# Greippi_pos_boost.net
KiCad netlist of a schematic drawn in EAGLE
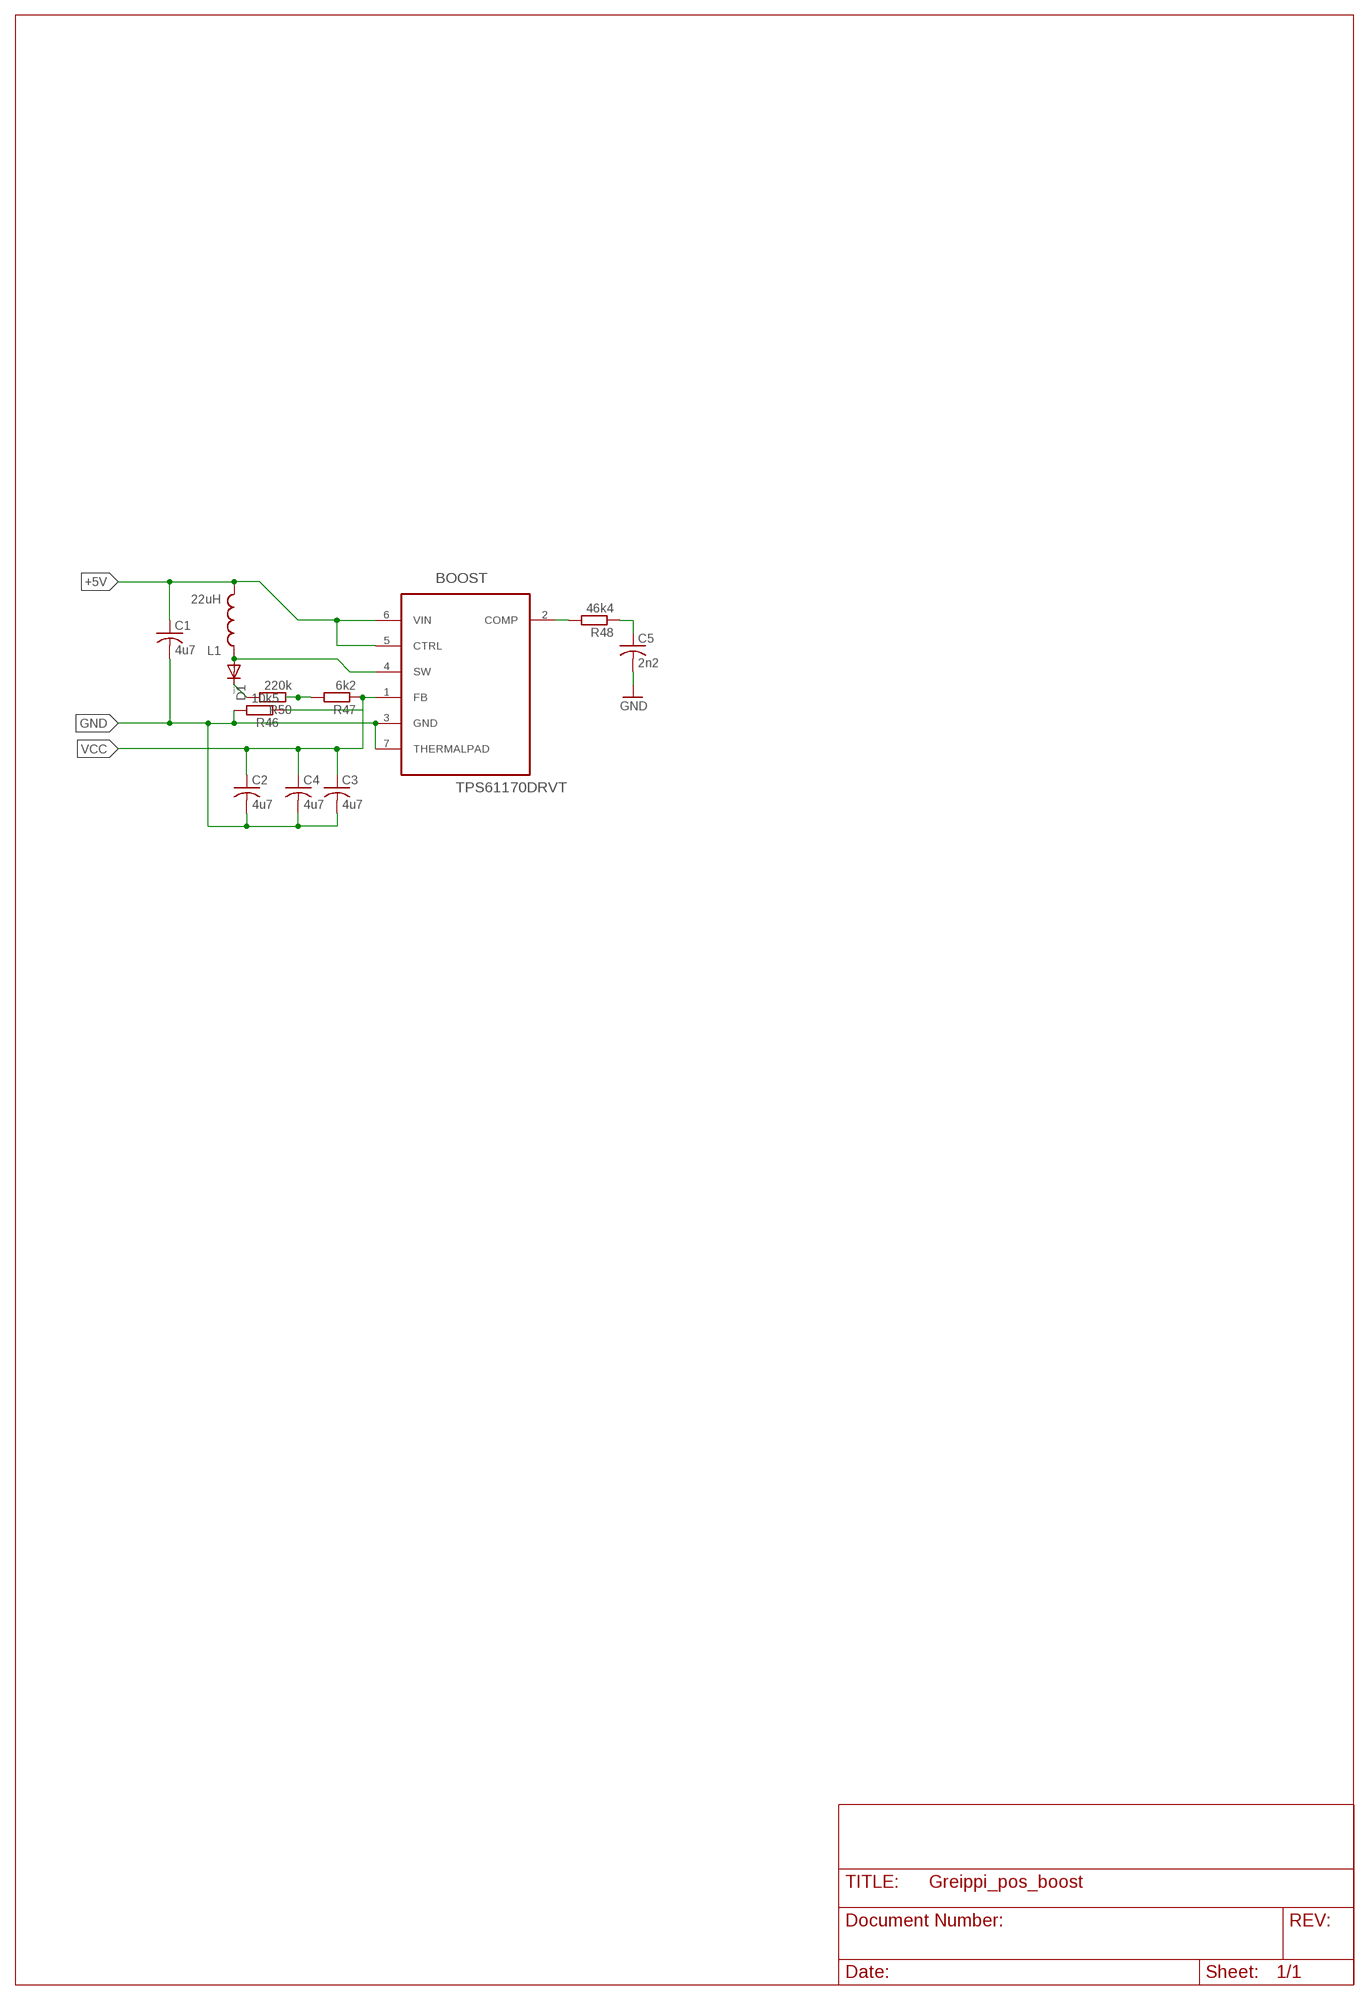
[diagram p0: schematic, sheet 1]

(export (version "E")
  (design (tool "Eeschema 10.0.6"))
  (components
    (comp (ref "BOOST")
      (value "TPS61170DRVT")
      (footprint "eagle-import:SON65P210X210X80-7N")
      (libsource (lib "eagle-import") (part "TPS61170DRVT"))
    )
    (comp (ref "C1")
      (value "4u7")
      (footprint "eagle-import:C1206")
      (libsource (lib "eagle-import") (part "C-USC1206"))
    )
    (comp (ref "C2")
      (value "4u7")
      (footprint "eagle-import:C0805")
      (libsource (lib "eagle-import") (part "C-USC0805"))
    )
    (comp (ref "C3")
      (value "4u7")
      (footprint "eagle-import:C1206")
      (libsource (lib "eagle-import") (part "C-USC1206"))
    )
    (comp (ref "C4")
      (value "4u7")
      (footprint "eagle-import:C1206")
      (libsource (lib "eagle-import") (part "C-USC1206"))
    )
    (comp (ref "C5")
      (value "2n2")
      (footprint "eagle-import:C1206")
      (libsource (lib "eagle-import") (part "C-USC1206"))
    )
    (comp (ref "D1")
      (value "DIODE-SOD123")
      (footprint "eagle-import:SOD123")
      (libsource (lib "eagle-import") (part "DIODE-SOD123"))
    )
    (comp (ref "L1")
      (value "22uH")
      (footprint "eagle-import:SRN6045")
      (libsource (lib "eagle-import") (part "INDUCTORBOURNS_SRN6045"))
    )
    (comp (ref "R46")
      (value "10k5")
      (footprint "eagle-import:R0805")
      (libsource (lib "eagle-import") (part "R-EU_R0805"))
    )
    (comp (ref "R47")
      (value "6k2")
      (footprint "eagle-import:R0805")
      (libsource (lib "eagle-import") (part "R-EU_R0805"))
    )
    (comp (ref "R48")
      (value "46k4")
      (footprint "eagle-import:R0805")
      (libsource (lib "eagle-import") (part "R-EU_R0805"))
    )
    (comp (ref "R50")
      (value "220k")
      (footprint "eagle-import:R0805")
      (libsource (lib "eagle-import") (part "R-EU_R0805"))
    )
  )
  (nets
    (net (code "1") (name "+5V") (class "Default")
      (node (ref "BOOST") (pin "5") (pinfunction "CTRL_5") (pintype "input"))
      (node (ref "BOOST") (pin "6") (pinfunction "VIN_6") (pintype "power_in"))
      (node (ref "C1") (pin "1") (pinfunction "1_1") (pintype "passive"))
      (node (ref "L1") (pin "2") (pinfunction "2_2") (pintype "passive"))
    )
    (net (code "2") (name "GND") (class "Default")
      (node (ref "BOOST") (pin "3") (pinfunction "GND_3") (pintype "passive"))
      (node (ref "BOOST") (pin "7") (pinfunction "THERMALPAD_7") (pintype "passive"))
      (node (ref "C1") (pin "2") (pinfunction "2_2") (pintype "passive"))
      (node (ref "C2") (pin "2") (pinfunction "2_2") (pintype "passive"))
      (node (ref "C3") (pin "2") (pinfunction "2_2") (pintype "passive"))
      (node (ref "C4") (pin "2") (pinfunction "2_2") (pintype "passive"))
      (node (ref "C5") (pin "2") (pinfunction "2_2") (pintype "passive"))
      (node (ref "R46") (pin "2") (pinfunction "2_2") (pintype "passive"))
    )
    (net (code "3") (name "Net-(BOOST-COMP)") (class "Default")
      (node (ref "BOOST") (pin "2") (pinfunction "COMP_2") (pintype "output"))
      (node (ref "R48") (pin "2") (pinfunction "2_2") (pintype "passive"))
    )
    (net (code "4") (name "Net-(BOOST-SW)") (class "Default")
      (node (ref "BOOST") (pin "4") (pinfunction "SW_4") (pintype "input"))
      (node (ref "D1") (pin "A") (pinfunction "A_A") (pintype "passive"))
      (node (ref "L1") (pin "1") (pinfunction "1_1") (pintype "passive"))
    )
    (net (code "5") (name "Net-(C5-Pad1)") (class "Default")
      (node (ref "C5") (pin "1") (pinfunction "1_1") (pintype "passive"))
      (node (ref "R48") (pin "1") (pinfunction "1_1") (pintype "passive"))
    )
    (net (code "6") (name "Net-(D1-PadC)") (class "Default")
      (node (ref "D1") (pin "C") (pinfunction "C_C") (pintype "passive"))
      (node (ref "R50") (pin "2") (pinfunction "2_2") (pintype "passive"))
    )
    (net (code "7") (name "Net-(R47-Pad2)") (class "Default")
      (node (ref "R47") (pin "2") (pinfunction "2_2") (pintype "passive"))
      (node (ref "R50") (pin "1") (pinfunction "1_1") (pintype "passive"))
    )
    (net (code "8") (name "VCC") (class "Default")
      (node (ref "BOOST") (pin "1") (pinfunction "FB_1") (pintype "input"))
      (node (ref "C2") (pin "1") (pinfunction "1_1") (pintype "passive"))
      (node (ref "C3") (pin "1") (pinfunction "1_1") (pintype "passive"))
      (node (ref "C4") (pin "1") (pinfunction "1_1") (pintype "passive"))
      (node (ref "R46") (pin "1") (pinfunction "1_1") (pintype "passive"))
      (node (ref "R47") (pin "1") (pinfunction "1_1") (pintype "passive"))
    )
  )
)
